# Videre.net
KiCad netlist of a schematic drawn in EAGLE
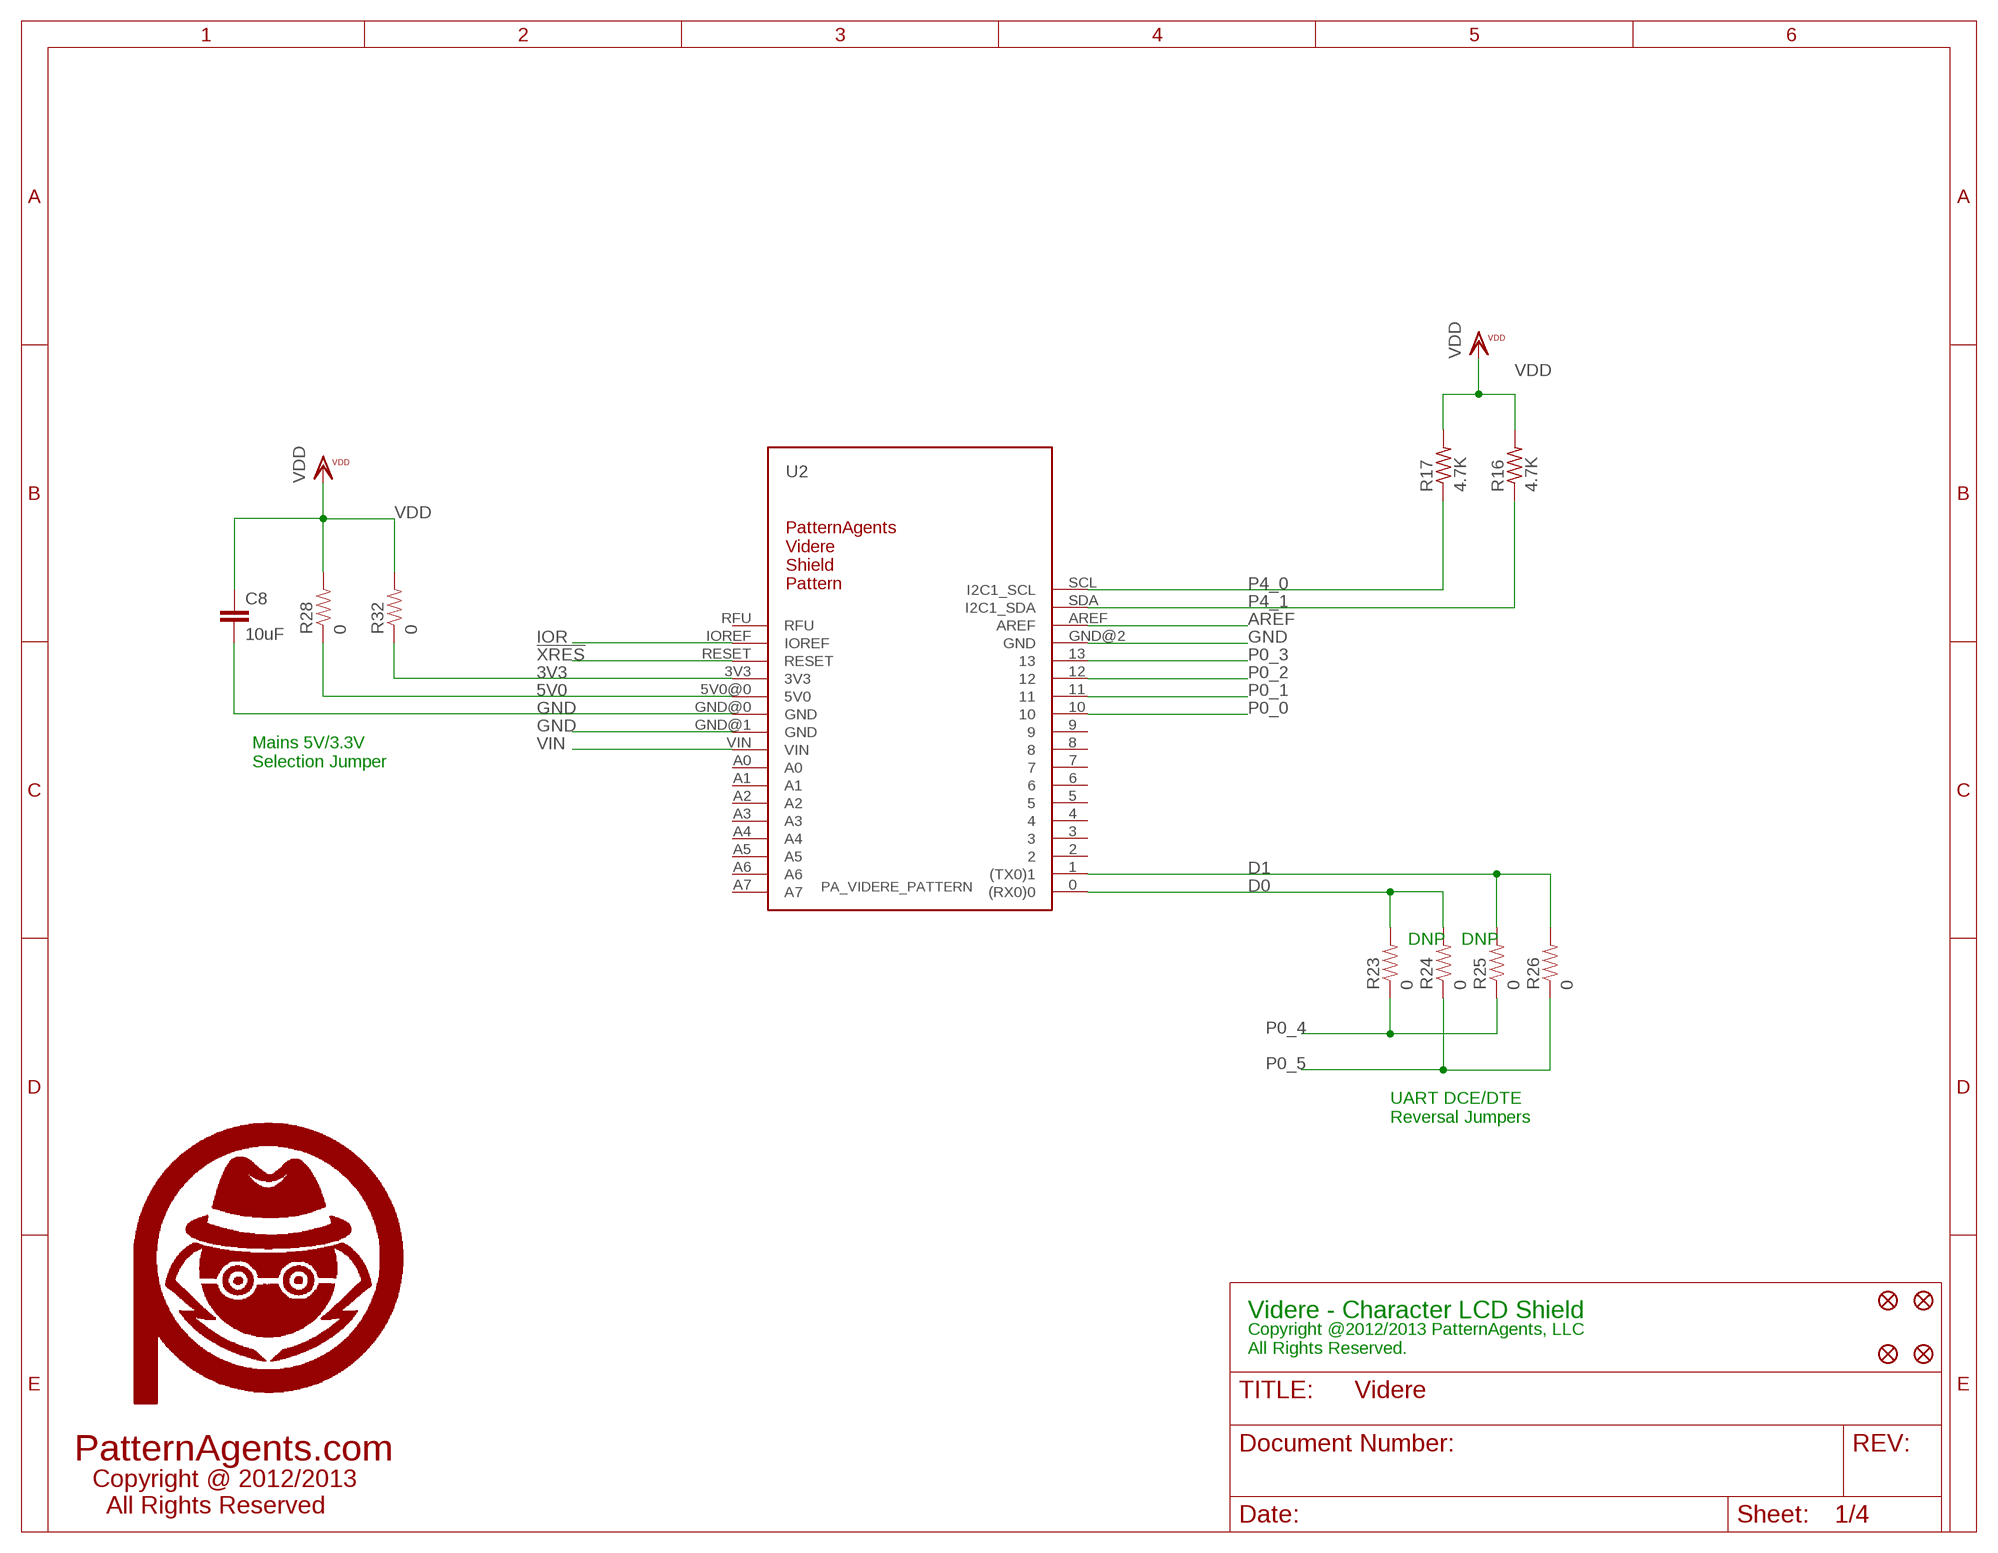
[diagram p0: schematic, sheet 1]
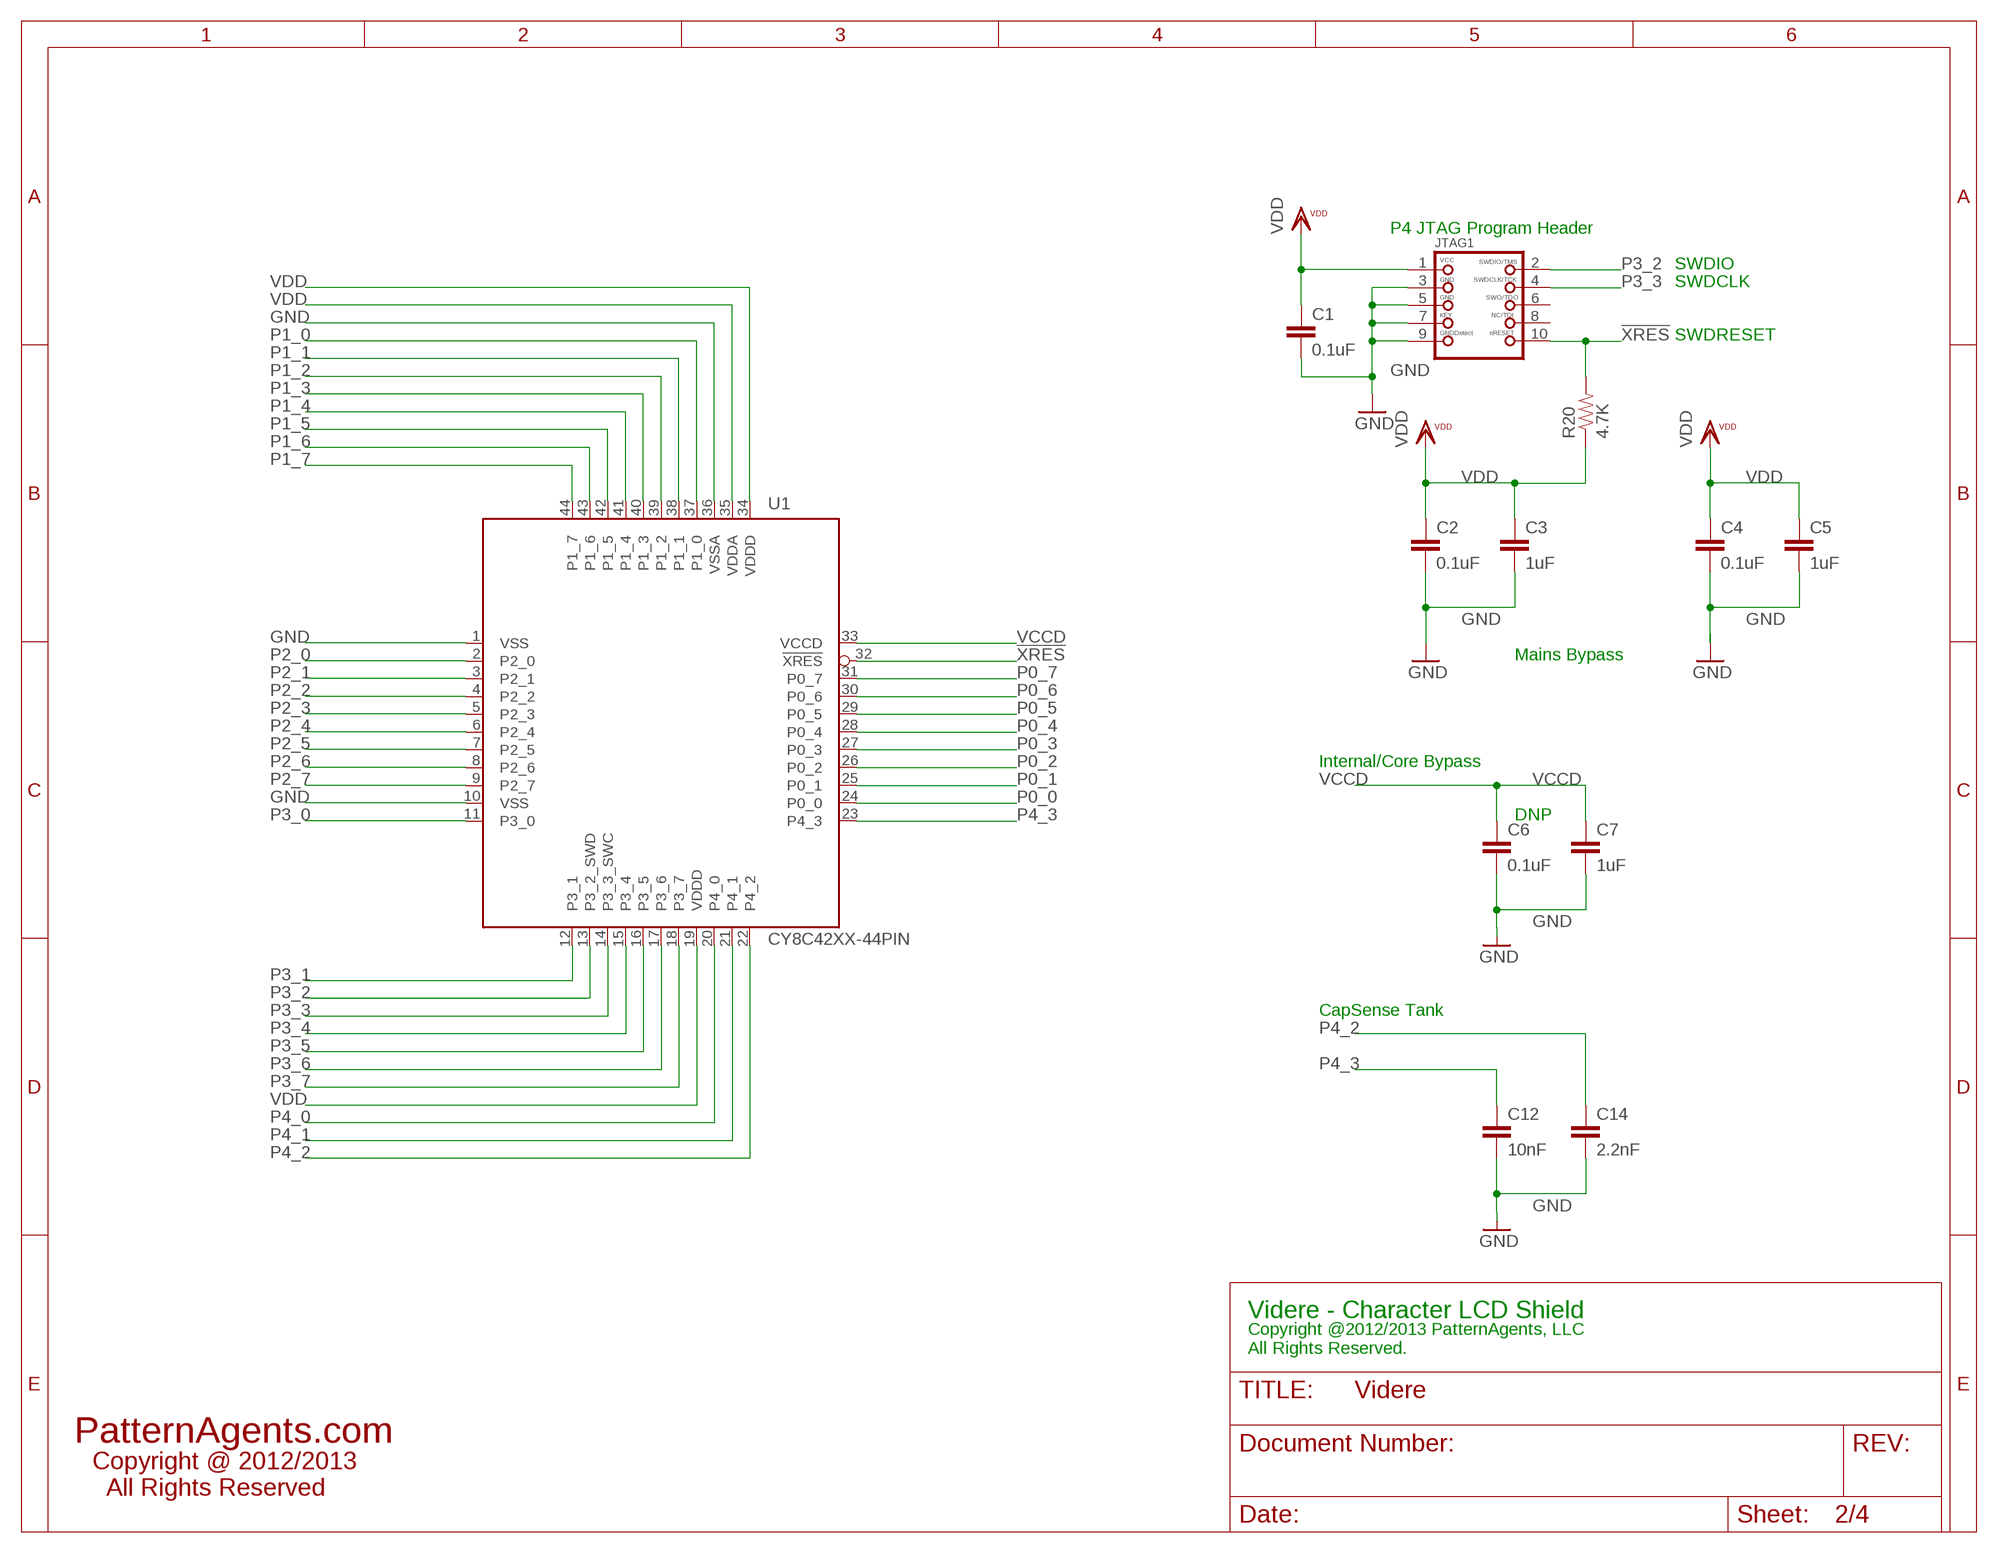
[diagram p1: schematic, sheet 2]
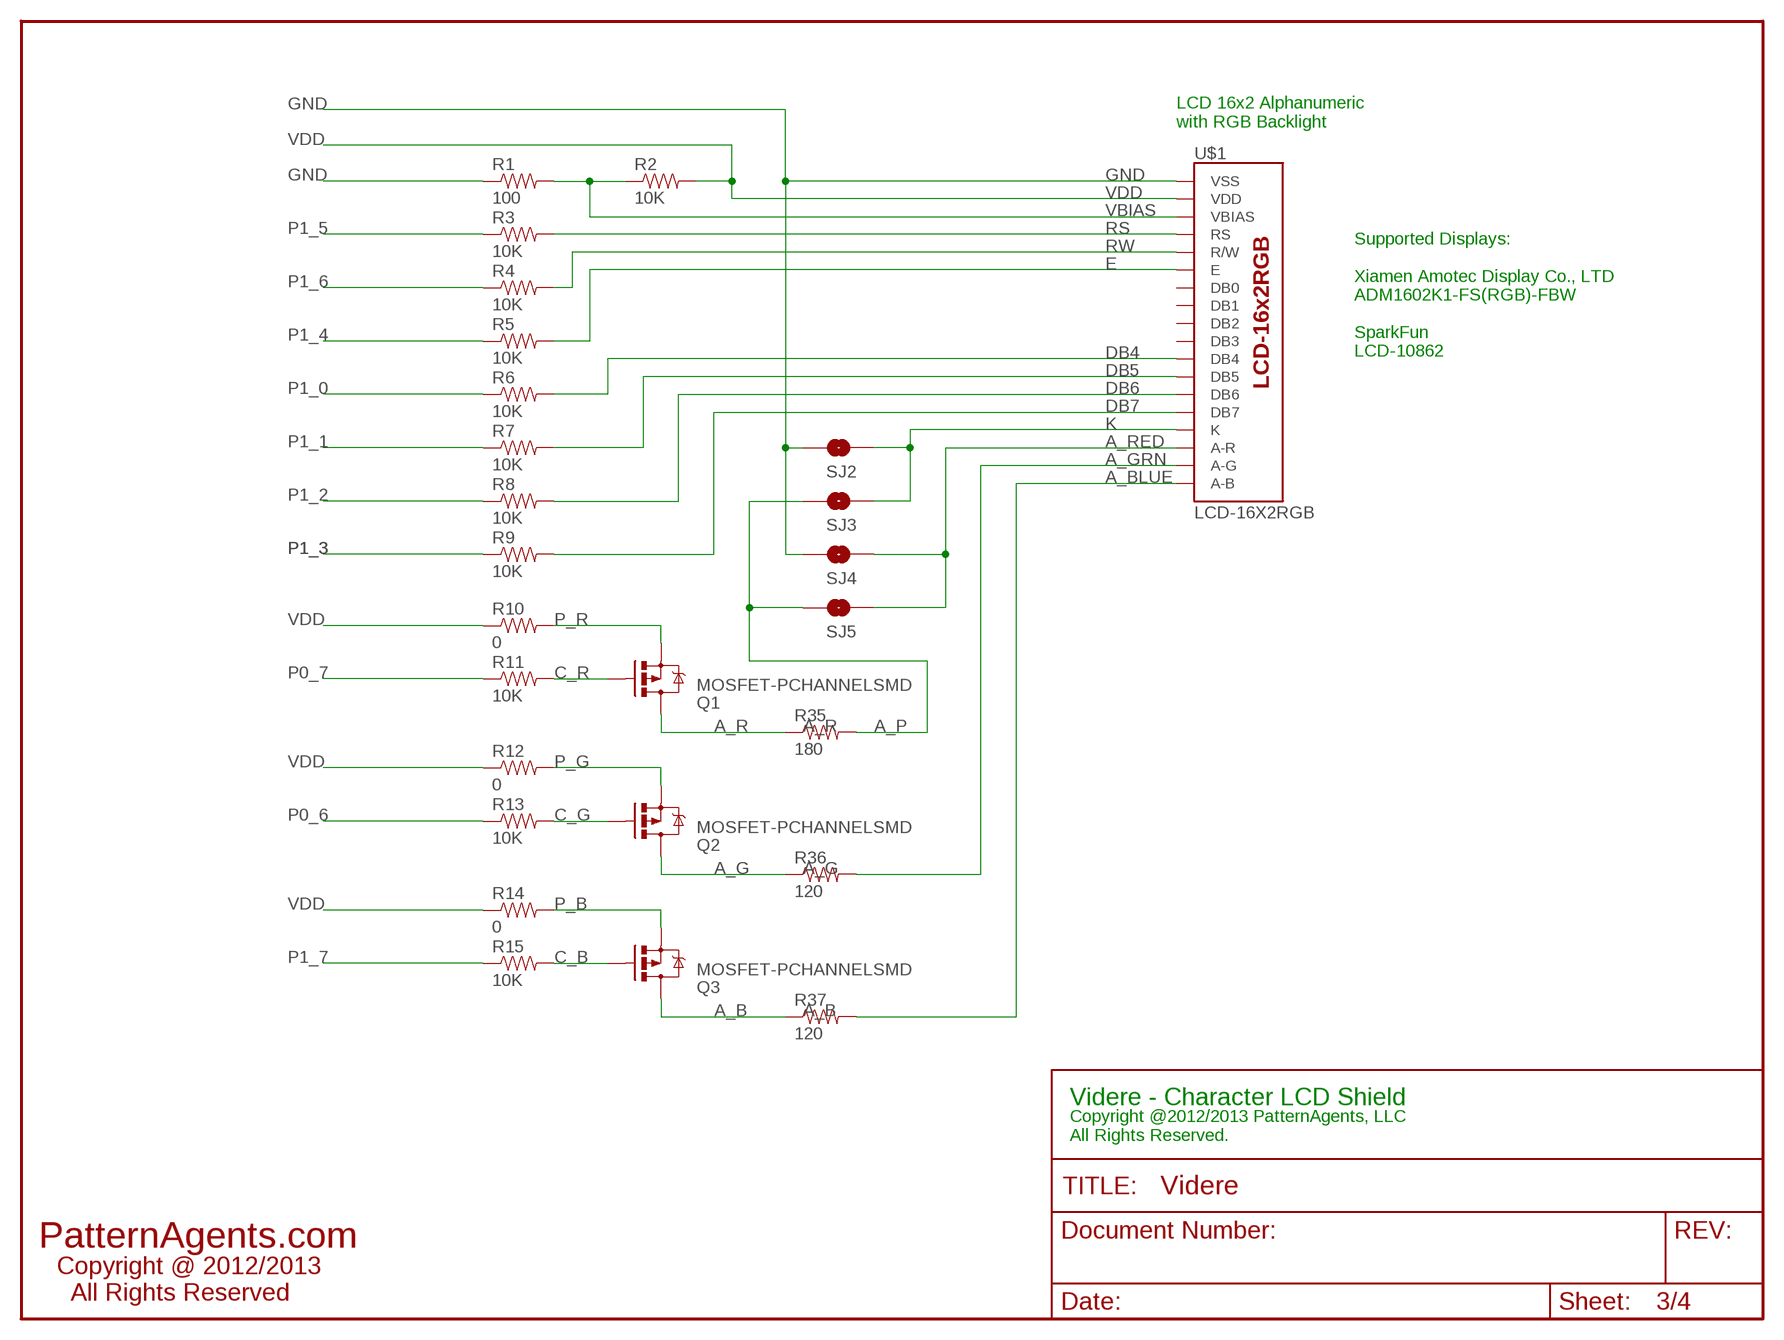
[diagram p2: schematic, sheet 3]
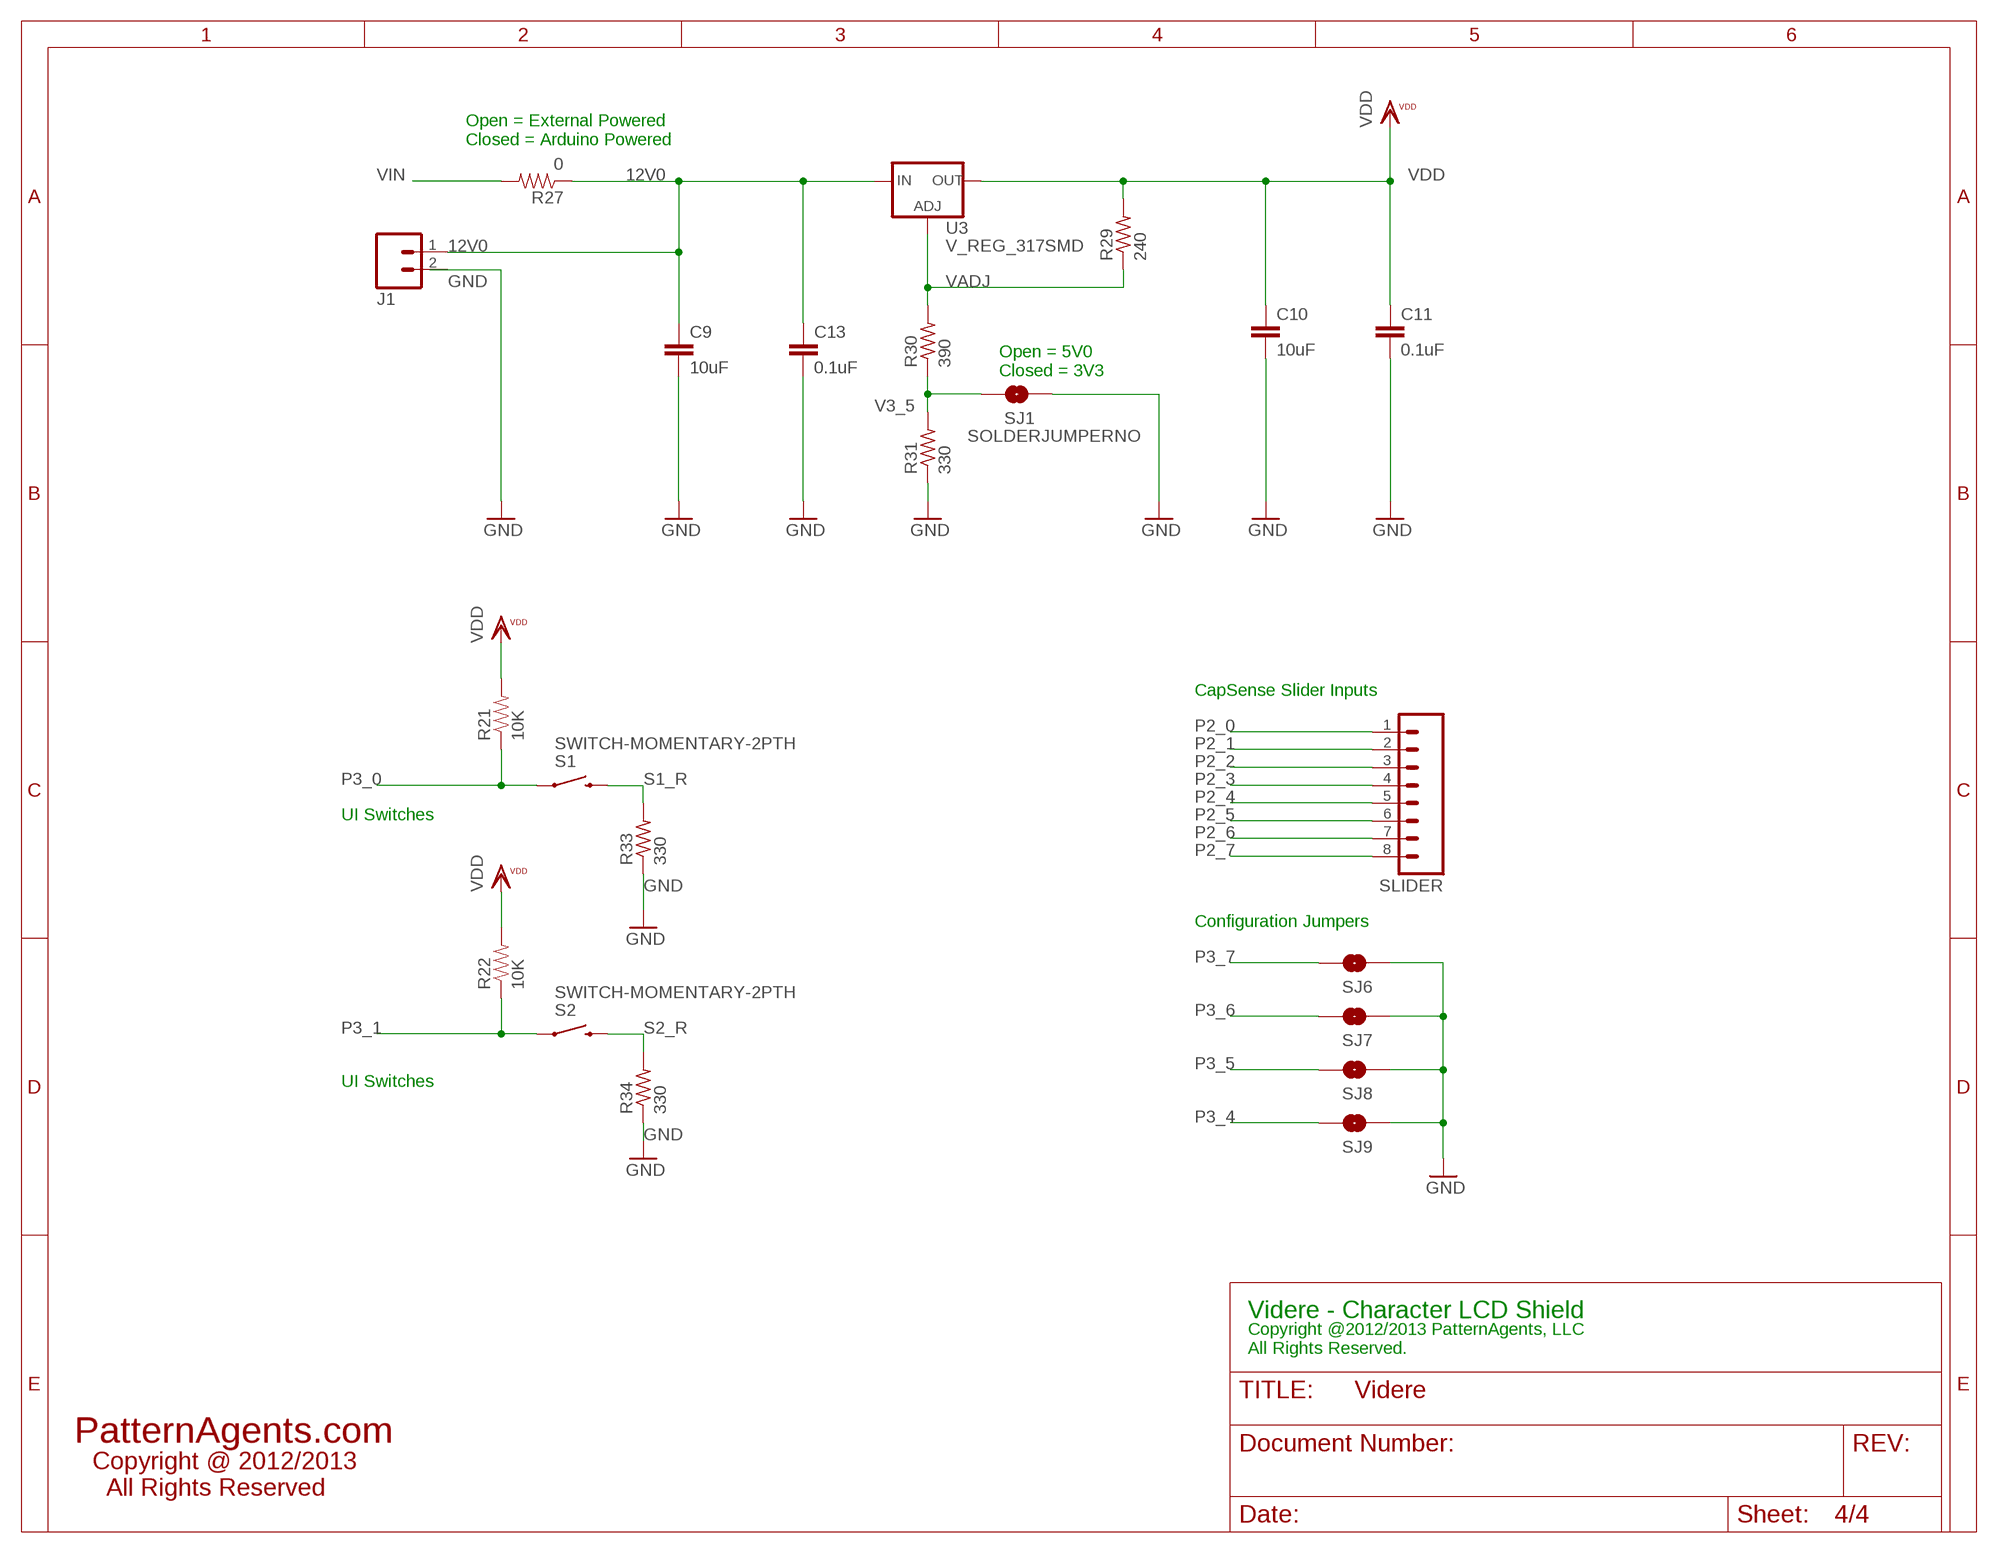
[diagram p3: schematic, sheet 4]

(export (version "E")
  (design (tool "Eeschema 10.0.6"))
  (components
    (comp (ref "C1")
      (value "0.1uF")
      (footprint "eagle-import:0603-CAP")
      (libsource (lib "eagle-import") (part "CAP0603-CAP"))
    )
    (comp (ref "C2")
      (value "0.1uF")
      (footprint "eagle-import:0603-CAP")
      (libsource (lib "eagle-import") (part "CAP0603-CAP"))
    )
    (comp (ref "C3")
      (value "1uF")
      (footprint "eagle-import:0603-CAP")
      (libsource (lib "eagle-import") (part "CAP0603-CAP"))
    )
    (comp (ref "C4")
      (value "0.1uF")
      (footprint "eagle-import:0603-CAP")
      (libsource (lib "eagle-import") (part "CAP0603-CAP"))
    )
    (comp (ref "C5")
      (value "1uF")
      (footprint "eagle-import:0603-CAP")
      (libsource (lib "eagle-import") (part "CAP0603-CAP"))
    )
    (comp (ref "C6")
      (value "0.1uF")
      (footprint "eagle-import:0603-CAP")
      (libsource (lib "eagle-import") (part "CAP0603-CAP"))
    )
    (comp (ref "C7")
      (value "1uF")
      (footprint "eagle-import:0603-CAP")
      (libsource (lib "eagle-import") (part "CAP0603-CAP"))
    )
    (comp (ref "C12")
      (value "10nF")
      (footprint "eagle-import:0603-CAP")
      (libsource (lib "eagle-import") (part "CAP0603-CAP"))
    )
    (comp (ref "C14")
      (value "2.2nF")
      (footprint "eagle-import:0603-CAP")
      (libsource (lib "eagle-import") (part "CAP0603-CAP"))
    )
    (comp (ref "JTAG1")
      (value "JTAG-CORTEXM3")
      (footprint "eagle-import:2X05_1.27MM_SMT")
      (libsource (lib "eagle-import") (part "JTAG-CORTEXM3"))
    )
    (comp (ref "R20")
      (value "4.7K")
      (footprint "eagle-import:0603-RES")
      (libsource (lib "eagle-import") (part "RESISTOR_SFE0603-RES"))
    )
    (comp (ref "U1")
      (value "CY8C42XX-44PIN")
      (footprint "eagle-import:TQFP-10X10-44")
      (libsource (lib "eagle-import") (part "CY8C42XX-44PIN"))
    )
    (comp (ref "Q1")
      (value "MOSFET-PCHANNELSMD")
      (footprint "eagle-import:SOT23-3")
      (libsource (lib "eagle-import") (part "MOSFET-PCHANNELSMD"))
    )
    (comp (ref "Q2")
      (value "MOSFET-PCHANNELSMD")
      (footprint "eagle-import:SOT23-3")
      (libsource (lib "eagle-import") (part "MOSFET-PCHANNELSMD"))
    )
    (comp (ref "Q3")
      (value "MOSFET-PCHANNELSMD")
      (footprint "eagle-import:SOT23-3")
      (libsource (lib "eagle-import") (part "MOSFET-PCHANNELSMD"))
    )
    (comp (ref "R1")
      (value "100")
      (footprint "eagle-import:0603-RES")
      (libsource (lib "eagle-import") (part "RESISTOR_SFE0603-RES"))
    )
    (comp (ref "R2")
      (value "10K")
      (footprint "eagle-import:0603-RES")
      (libsource (lib "eagle-import") (part "RESISTOR_SFE0603-RES"))
    )
    (comp (ref "R3")
      (value "10K")
      (footprint "eagle-import:0603-RES")
      (libsource (lib "eagle-import") (part "RESISTOR_SFE0603-RES"))
    )
    (comp (ref "R4")
      (value "10K")
      (footprint "eagle-import:0603-RES")
      (libsource (lib "eagle-import") (part "RESISTOR_SFE0603-RES"))
    )
    (comp (ref "R5")
      (value "10K")
      (footprint "eagle-import:0603-RES")
      (libsource (lib "eagle-import") (part "RESISTOR_SFE0603-RES"))
    )
    (comp (ref "R6")
      (value "10K")
      (footprint "eagle-import:0603-RES")
      (libsource (lib "eagle-import") (part "RESISTOR_SFE0603-RES"))
    )
    (comp (ref "R7")
      (value "10K")
      (footprint "eagle-import:0603-RES")
      (libsource (lib "eagle-import") (part "RESISTOR_SFE0603-RES"))
    )
    (comp (ref "R8")
      (value "10K")
      (footprint "eagle-import:0603-RES")
      (libsource (lib "eagle-import") (part "RESISTOR_SFE0603-RES"))
    )
    (comp (ref "R9")
      (value "10K")
      (footprint "eagle-import:0603-RES")
      (libsource (lib "eagle-import") (part "RESISTOR_SFE0603-RES"))
    )
    (comp (ref "R10")
      (value "0")
      (footprint "eagle-import:0603-RES")
      (libsource (lib "eagle-import") (part "RESISTOR_SFE0603-RES"))
    )
    (comp (ref "R11")
      (value "10K")
      (footprint "eagle-import:0603-RES")
      (libsource (lib "eagle-import") (part "RESISTOR_SFE0603-RES"))
    )
    (comp (ref "R12")
      (value "0")
      (footprint "eagle-import:0603-RES")
      (libsource (lib "eagle-import") (part "RESISTOR_SFE0603-RES"))
    )
    (comp (ref "R13")
      (value "10K")
      (footprint "eagle-import:0603-RES")
      (libsource (lib "eagle-import") (part "RESISTOR_SFE0603-RES"))
    )
    (comp (ref "R14")
      (value "0")
      (footprint "eagle-import:0603-RES")
      (libsource (lib "eagle-import") (part "RESISTOR_SFE0603-RES"))
    )
    (comp (ref "R15")
      (value "10K")
      (footprint "eagle-import:0603-RES")
      (libsource (lib "eagle-import") (part "RESISTOR_SFE0603-RES"))
    )
    (comp (ref "R35")
      (value "180")
      (footprint "eagle-import:0603-RES")
      (libsource (lib "eagle-import") (part "RESISTOR_SFE0603-RES"))
    )
    (comp (ref "R36")
      (value "120")
      (footprint "eagle-import:0603-RES")
      (libsource (lib "eagle-import") (part "RESISTOR_SFE0603-RES"))
    )
    (comp (ref "R37")
      (value "120")
      (footprint "eagle-import:0603-RES")
      (libsource (lib "eagle-import") (part "RESISTOR_SFE0603-RES"))
    )
    (comp (ref "SJ2")
      (value "SOLDERJUMPERNO")
      (footprint "eagle-import:SJ_2S-NO")
      (libsource (lib "eagle-import") (part "SOLDERJUMPERNO"))
    )
    (comp (ref "SJ3")
      (value "SOLDERJUMPERNO")
      (footprint "eagle-import:SJ_2S-NO")
      (libsource (lib "eagle-import") (part "SOLDERJUMPERNO"))
    )
    (comp (ref "SJ4")
      (value "SOLDERJUMPERNO")
      (footprint "eagle-import:SJ_2S-NO")
      (libsource (lib "eagle-import") (part "SOLDERJUMPERNO"))
    )
    (comp (ref "SJ5")
      (value "SOLDERJUMPERNO")
      (footprint "eagle-import:SJ_2S-NO")
      (libsource (lib "eagle-import") (part "SOLDERJUMPERNO"))
    )
    (comp (ref "U$1")
      (value "LCD-16X2RGB")
      (footprint "eagle-import:LCD-16X2RGB")
      (libsource (lib "eagle-import") (part "LCD-16X2RGB"))
    )
    (comp (ref "C9")
      (value "10uF")
      (footprint "eagle-import:1210")
      (libsource (lib "eagle-import") (part "CAP1210"))
    )
    (comp (ref "C10")
      (value "10uF")
      (footprint "eagle-import:1210")
      (libsource (lib "eagle-import") (part "CAP1210"))
    )
    (comp (ref "C11")
      (value "0.1uF")
      (footprint "eagle-import:0603-CAP")
      (libsource (lib "eagle-import") (part "CAP0603-CAP"))
    )
    (comp (ref "C13")
      (value "0.1uF")
      (footprint "eagle-import:0603-CAP")
      (libsource (lib "eagle-import") (part "CAP0603-CAP"))
    )
    (comp (ref "J1")
      (value "M02PTH")
      (footprint "eagle-import:1X02")
      (libsource (lib "eagle-import") (part "M02PTH"))
    )
    (comp (ref "R21")
      (value "10K")
      (footprint "eagle-import:0603-RES")
      (libsource (lib "eagle-import") (part "RESISTOR_SFE0603-RES"))
    )
    (comp (ref "R22")
      (value "10K")
      (footprint "eagle-import:0603-RES")
      (libsource (lib "eagle-import") (part "RESISTOR_SFE0603-RES"))
    )
    (comp (ref "R27")
      (value "0")
      (footprint "eagle-import:0603-RES")
      (libsource (lib "eagle-import") (part "RESISTOR_SFE0603-RES"))
    )
    (comp (ref "R29")
      (value "240")
      (footprint "eagle-import:R0603")
      (libsource (lib "eagle-import") (part "RESISTORR0603"))
    )
    (comp (ref "R30")
      (value "390")
      (footprint "eagle-import:R0603")
      (libsource (lib "eagle-import") (part "RESISTORR0603"))
    )
    (comp (ref "R31")
      (value "330")
      (footprint "eagle-import:R0603")
      (libsource (lib "eagle-import") (part "RESISTORR0603"))
    )
    (comp (ref "R33")
      (value "330")
      (footprint "eagle-import:R0603")
      (libsource (lib "eagle-import") (part "RESISTORR0603"))
    )
    (comp (ref "R34")
      (value "330")
      (footprint "eagle-import:R0603")
      (libsource (lib "eagle-import") (part "RESISTORR0603"))
    )
    (comp (ref "S1")
      (value "SWITCH-MOMENTARY-2PTH")
      (footprint "eagle-import:TACTILE-PTH")
      (libsource (lib "eagle-import") (part "SWITCH-MOMENTARY-2PTH"))
    )
    (comp (ref "S2")
      (value "SWITCH-MOMENTARY-2PTH")
      (footprint "eagle-import:TACTILE-PTH")
      (libsource (lib "eagle-import") (part "SWITCH-MOMENTARY-2PTH"))
    )
    (comp (ref "SJ1")
      (value "SOLDERJUMPERNO")
      (footprint "eagle-import:SJ_2S-NO")
      (libsource (lib "eagle-import") (part "SOLDERJUMPERNO"))
    )
    (comp (ref "SJ6")
      (value "SOLDERJUMPERNO")
      (footprint "eagle-import:SJ_2S-NO")
      (libsource (lib "eagle-import") (part "SOLDERJUMPERNO"))
    )
    (comp (ref "SJ7")
      (value "SOLDERJUMPERNO")
      (footprint "eagle-import:SJ_2S-NO")
      (libsource (lib "eagle-import") (part "SOLDERJUMPERNO"))
    )
    (comp (ref "SJ8")
      (value "SOLDERJUMPERNO")
      (footprint "eagle-import:SJ_2S-NO")
      (libsource (lib "eagle-import") (part "SOLDERJUMPERNO"))
    )
    (comp (ref "SJ9")
      (value "SOLDERJUMPERNO")
      (footprint "eagle-import:SJ_2S-NO")
      (libsource (lib "eagle-import") (part "SOLDERJUMPERNO"))
    )
    (comp (ref "SLIDER")
      (value "M081X08")
      (footprint "eagle-import:1X08")
      (libsource (lib "eagle-import") (part "M081X08"))
    )
    (comp (ref "U3")
      (value "V_REG_317SMD")
      (footprint "eagle-import:SOT223")
      (libsource (lib "eagle-import") (part "V_REG_317SMD"))
    )
    (comp (ref "C8")
      (value "10uF")
      (footprint "eagle-import:1210")
      (libsource (lib "eagle-import") (part "CAP1210"))
    )
    (comp (ref "FID1")
      (value "FIDUCIAL1.5X3")
      (footprint "eagle-import:FIDUCIAL-1.5X3")
      (libsource (lib "eagle-import") (part "FIDUCIAL1.5X3"))
    )
    (comp (ref "FID2")
      (value "FIDUCIAL1.5X3")
      (footprint "eagle-import:FIDUCIAL-1.5X3")
      (libsource (lib "eagle-import") (part "FIDUCIAL1.5X3"))
    )
    (comp (ref "FID3")
      (value "FIDUCIAL1.5X3")
      (footprint "eagle-import:FIDUCIAL-1.5X3")
      (libsource (lib "eagle-import") (part "FIDUCIAL1.5X3"))
    )
    (comp (ref "FID4")
      (value "FIDUCIAL1.5X3")
      (footprint "eagle-import:FIDUCIAL-1.5X3")
      (libsource (lib "eagle-import") (part "FIDUCIAL1.5X3"))
    )
    (comp (ref "R16")
      (value "4.7K")
      (footprint "eagle-import:R0603")
      (libsource (lib "eagle-import") (part "RESISTORR0603"))
    )
    (comp (ref "R17")
      (value "4.7K")
      (footprint "eagle-import:R0603")
      (libsource (lib "eagle-import") (part "RESISTORR0603"))
    )
    (comp (ref "R23")
      (value "0")
      (footprint "eagle-import:0603-RES")
      (libsource (lib "eagle-import") (part "RESISTOR_SFE0603-RES"))
    )
    (comp (ref "R24")
      (value "0")
      (footprint "eagle-import:0603-RES")
      (libsource (lib "eagle-import") (part "RESISTOR_SFE0603-RES"))
    )
    (comp (ref "R25")
      (value "0")
      (footprint "eagle-import:0603-RES")
      (libsource (lib "eagle-import") (part "RESISTOR_SFE0603-RES"))
    )
    (comp (ref "R26")
      (value "0")
      (footprint "eagle-import:0603-RES")
      (libsource (lib "eagle-import") (part "RESISTOR_SFE0603-RES"))
    )
    (comp (ref "R28")
      (value "0")
      (footprint "eagle-import:0603-RES@1")
      (libsource (lib "eagle-import") (part "moxdes_std_RESISTOR_SFE0603-RES"))
    )
    (comp (ref "R32")
      (value "0")
      (footprint "eagle-import:0603-RES@1")
      (libsource (lib "eagle-import") (part "moxdes_std_RESISTOR_SFE0603-RES"))
    )
    (comp (ref "U$3")
      (value "PA_LOGO_SYMLARGE")
      (footprint "eagle-import:PA_LOGO_AGENT_LRG_SYM")
      (libsource (lib "eagle-import") (part "PA_LOGO_SYMLARGE"))
    )
    (comp (ref "U2")
      (value "PA_VIDERE_PATTERN")
      (footprint "eagle-import:PA_VIDERE_PATTERN")
      (libsource (lib "eagle-import") (part "PA_VIDERE_PATTERN"))
    )
  )
  (nets
    (net (code "1") (name "3V3") (class "Default")
      (node (ref "R32") (pin "1") (pinfunction "1_1") (pintype "passive"))
      (node (ref "U2") (pin "3V3") (pinfunction "3V3_3V3") (pintype "bidirectional"))
    )
    (net (code "2") (name "5V0") (class "Default")
      (node (ref "R28") (pin "1") (pinfunction "1_1") (pintype "passive"))
      (node (ref "U2") (pin "5V0@0") (pinfunction "5V0_5V0@0") (pintype "bidirectional"))
    )
    (net (code "3") (name "12V0") (class "Default")
      (node (ref "C13") (pin "1") (pinfunction "1_1") (pintype "passive"))
      (node (ref "C9") (pin "1") (pinfunction "1_1") (pintype "passive"))
      (node (ref "J1") (pin "1") (pinfunction "1_1") (pintype "passive"))
      (node (ref "R27") (pin "1") (pinfunction "1_1") (pintype "passive"))
      (node (ref "U3") (pin "3") (pinfunction "IN_3") (pintype "input"))
    )
    (net (code "4") (name "AREF") (class "Default")
      (node (ref "U2") (pin "AREF") (pinfunction "AREF_AREF") (pintype "bidirectional"))
    )
    (net (code "5") (name "A_B") (class "Default")
      (node (ref "Q3") (pin "3") (pinfunction "D_3") (pintype "passive"))
      (node (ref "R37") (pin "1") (pinfunction "1_1") (pintype "passive"))
    )
    (net (code "6") (name "A_BLUE") (class "Default")
      (node (ref "R37") (pin "2") (pinfunction "2_2") (pintype "passive"))
      (node (ref "U$1") (pin "18") (pinfunction "A-B_18") (pintype "power_in"))
    )
    (net (code "7") (name "A_G") (class "Default")
      (node (ref "Q2") (pin "3") (pinfunction "D_3") (pintype "passive"))
      (node (ref "R36") (pin "1") (pinfunction "1_1") (pintype "passive"))
    )
    (net (code "8") (name "A_GRN") (class "Default")
      (node (ref "R36") (pin "2") (pinfunction "2_2") (pintype "passive"))
      (node (ref "U$1") (pin "17") (pinfunction "A-G_17") (pintype "power_in"))
    )
    (net (code "9") (name "A_P") (class "Default")
      (node (ref "R35") (pin "2") (pinfunction "2_2") (pintype "passive"))
      (node (ref "SJ3") (pin "2") (pinfunction "2_2") (pintype "passive"))
      (node (ref "SJ5") (pin "2") (pinfunction "2_2") (pintype "passive"))
    )
    (net (code "10") (name "A_R") (class "Default")
      (node (ref "Q1") (pin "3") (pinfunction "D_3") (pintype "passive"))
      (node (ref "R35") (pin "1") (pinfunction "1_1") (pintype "passive"))
    )
    (net (code "11") (name "A_RED") (class "Default")
      (node (ref "SJ4") (pin "1") (pinfunction "1_1") (pintype "passive"))
      (node (ref "SJ5") (pin "1") (pinfunction "1_1") (pintype "passive"))
      (node (ref "U$1") (pin "16") (pinfunction "A-R_16") (pintype "power_in"))
    )
    (net (code "12") (name "C_B") (class "Default")
      (node (ref "Q3") (pin "1") (pinfunction "G_1") (pintype "passive"))
      (node (ref "R15") (pin "2") (pinfunction "2_2") (pintype "passive"))
    )
    (net (code "13") (name "C_G") (class "Default")
      (node (ref "Q2") (pin "1") (pinfunction "G_1") (pintype "passive"))
      (node (ref "R13") (pin "2") (pinfunction "2_2") (pintype "passive"))
    )
    (net (code "14") (name "C_R") (class "Default")
      (node (ref "Q1") (pin "1") (pinfunction "G_1") (pintype "passive"))
      (node (ref "R11") (pin "2") (pinfunction "2_2") (pintype "passive"))
    )
    (net (code "15") (name "D0") (class "Default")
      (node (ref "R23") (pin "2") (pinfunction "2_2") (pintype "passive"))
      (node (ref "R24") (pin "2") (pinfunction "2_2") (pintype "passive"))
      (node (ref "U2") (pin "0") (pinfunction "(RX0)0_0") (pintype "bidirectional"))
    )
    (net (code "16") (name "D1") (class "Default")
      (node (ref "R25") (pin "2") (pinfunction "2_2") (pintype "passive"))
      (node (ref "R26") (pin "2") (pinfunction "2_2") (pintype "passive"))
      (node (ref "U2") (pin "1") (pinfunction "(TX0)1_1") (pintype "bidirectional"))
    )
    (net (code "17") (name "DB4") (class "Default")
      (node (ref "R6") (pin "2") (pinfunction "2_2") (pintype "passive"))
      (node (ref "U$1") (pin "11") (pinfunction "DB4_11") (pintype "bidirectional"))
    )
    (net (code "18") (name "DB5") (class "Default")
      (node (ref "R7") (pin "2") (pinfunction "2_2") (pintype "passive"))
      (node (ref "U$1") (pin "12") (pinfunction "DB5_12") (pintype "bidirectional"))
    )
    (net (code "19") (name "DB6") (class "Default")
      (node (ref "R8") (pin "2") (pinfunction "2_2") (pintype "passive"))
      (node (ref "U$1") (pin "13") (pinfunction "DB6_13") (pintype "bidirectional"))
    )
    (net (code "20") (name "DB7") (class "Default")
      (node (ref "R9") (pin "2") (pinfunction "2_2") (pintype "passive"))
      (node (ref "U$1") (pin "14") (pinfunction "DB7_14") (pintype "bidirectional"))
    )
    (net (code "21") (name "E") (class "Default")
      (node (ref "R5") (pin "2") (pinfunction "2_2") (pintype "passive"))
      (node (ref "U$1") (pin "6") (pinfunction "E_6") (pintype "input"))
    )
    (net (code "22") (name "GND") (class "Default")
      (node (ref "C1") (pin "2") (pinfunction "2_2") (pintype "passive"))
      (node (ref "C10") (pin "2") (pinfunction "2_2") (pintype "passive"))
      (node (ref "C11") (pin "2") (pinfunction "2_2") (pintype "passive"))
      (node (ref "C12") (pin "2") (pinfunction "2_2") (pintype "passive"))
      (node (ref "C13") (pin "2") (pinfunction "2_2") (pintype "passive"))
      (node (ref "C14") (pin "2") (pinfunction "2_2") (pintype "passive"))
      (node (ref "C2") (pin "2") (pinfunction "2_2") (pintype "passive"))
      (node (ref "C3") (pin "2") (pinfunction "2_2") (pintype "passive"))
      (node (ref "C4") (pin "2") (pinfunction "2_2") (pintype "passive"))
      (node (ref "C5") (pin "2") (pinfunction "2_2") (pintype "passive"))
      (node (ref "C6") (pin "2") (pinfunction "2_2") (pintype "passive"))
      (node (ref "C7") (pin "2") (pinfunction "2_2") (pintype "passive"))
      (node (ref "C8") (pin "2") (pinfunction "2_2") (pintype "passive"))
      (node (ref "C9") (pin "2") (pinfunction "2_2") (pintype "passive"))
      (node (ref "J1") (pin "2") (pinfunction "2_2") (pintype "passive"))
      (node (ref "JTAG1") (pin "3") (pinfunction "3_3") (pintype "passive"))
      (node (ref "JTAG1") (pin "5") (pinfunction "5_5") (pintype "passive"))
      (node (ref "JTAG1") (pin "7") (pinfunction "7_7") (pintype "passive"))
      (node (ref "JTAG1") (pin "9") (pinfunction "9_9") (pintype "passive"))
      (node (ref "R1") (pin "1") (pinfunction "1_1") (pintype "passive"))
      (node (ref "R31") (pin "1") (pinfunction "1_1") (pintype "passive"))
      (node (ref "R33") (pin "1") (pinfunction "1_1") (pintype "passive"))
      (node (ref "R34") (pin "1") (pinfunction "1_1") (pintype "passive"))
      (node (ref "SJ1") (pin "1") (pinfunction "1_1") (pintype "passive"))
      (node (ref "SJ2") (pin "2") (pinfunction "2_2") (pintype "passive"))
      (node (ref "SJ4") (pin "2") (pinfunction "2_2") (pintype "passive"))
      (node (ref "SJ6") (pin "1") (pinfunction "1_1") (pintype "passive"))
      (node (ref "SJ7") (pin "1") (pinfunction "1_1") (pintype "passive"))
      (node (ref "SJ8") (pin "1") (pinfunction "1_1") (pintype "passive"))
      (node (ref "SJ9") (pin "1") (pinfunction "1_1") (pintype "passive"))
      (node (ref "U$1") (pin "1") (pinfunction "VSS_1") (pintype "power_in"))
      (node (ref "U1") (pin "1") (pinfunction "VSS_1") (pintype "bidirectional"))
      (node (ref "U1") (pin "10") (pinfunction "VSS_10") (pintype "bidirectional"))
      (node (ref "U1") (pin "36") (pinfunction "VSSA_36") (pintype "bidirectional"))
      (node (ref "U2") (pin "GND@0") (pinfunction "GND_GND@0") (pintype "bidirectional"))
      (node (ref "U2") (pin "GND@1") (pinfunction "GND_GND@1") (pintype "bidirectional"))
      (node (ref "U2") (pin "GND@2") (pinfunction "GND_GND@2") (pintype "bidirectional"))
    )
    (net (code "23") (name "IOR") (class "Default")
      (node (ref "U2") (pin "IOREF") (pinfunction "IOREF_IOREF") (pintype "output"))
    )
    (net (code "24") (name "K") (class "Default")
      (node (ref "SJ2") (pin "1") (pinfunction "1_1") (pintype "passive"))
      (node (ref "SJ3") (pin "1") (pinfunction "1_1") (pintype "passive"))
      (node (ref "U$1") (pin "15") (pinfunction "K_15") (pintype "power_in"))
    )
    (net (code "25") (name "P0_0") (class "Default")
      (node (ref "U1") (pin "24") (pinfunction "P0_0_24") (pintype "bidirectional"))
      (node (ref "U2") (pin "10") (pinfunction "10_10") (pintype "bidirectional"))
    )
    (net (code "26") (name "P0_1") (class "Default")
      (node (ref "U1") (pin "25") (pinfunction "P0_1_25") (pintype "bidirectional"))
      (node (ref "U2") (pin "11") (pinfunction "11_11") (pintype "bidirectional"))
    )
    (net (code "27") (name "P0_2") (class "Default")
      (node (ref "U1") (pin "26") (pinfunction "P0_2_26") (pintype "input"))
      (node (ref "U2") (pin "12") (pinfunction "12_12") (pintype "bidirectional"))
    )
    (net (code "28") (name "P0_3") (class "Default")
      (node (ref "U1") (pin "27") (pinfunction "P0_3_27") (pintype "bidirectional"))
      (node (ref "U2") (pin "13") (pinfunction "13_13") (pintype "bidirectional"))
    )
    (net (code "29") (name "P0_4") (class "Default")
      (node (ref "R23") (pin "1") (pinfunction "1_1") (pintype "passive"))
      (node (ref "R25") (pin "1") (pinfunction "1_1") (pintype "passive"))
      (node (ref "U1") (pin "28") (pinfunction "P0_4_28") (pintype "bidirectional"))
    )
    (net (code "30") (name "P0_5") (class "Default")
      (node (ref "R24") (pin "1") (pinfunction "1_1") (pintype "passive"))
      (node (ref "R26") (pin "1") (pinfunction "1_1") (pintype "passive"))
      (node (ref "U1") (pin "29") (pinfunction "P0_5_29") (pintype "bidirectional"))
    )
    (net (code "31") (name "P0_6") (class "Default")
      (node (ref "R13") (pin "1") (pinfunction "1_1") (pintype "passive"))
      (node (ref "U1") (pin "30") (pinfunction "P0_6_30") (pintype "power_in"))
    )
    (net (code "32") (name "P0_7") (class "Default")
      (node (ref "R11") (pin "1") (pinfunction "1_1") (pintype "passive"))
      (node (ref "U1") (pin "31") (pinfunction "P0_7_31") (pintype "bidirectional"))
    )
    (net (code "33") (name "P1_0") (class "Default")
      (node (ref "R6") (pin "1") (pinfunction "1_1") (pintype "passive"))
      (node (ref "U1") (pin "37") (pinfunction "P1_0_37") (pintype "bidirectional"))
    )
    (net (code "34") (name "P1_1") (class "Default")
      (node (ref "R7") (pin "1") (pinfunction "1_1") (pintype "passive"))
      (node (ref "U1") (pin "38") (pinfunction "P1_1_38") (pintype "bidirectional"))
    )
    (net (code "35") (name "P1_2") (class "Default")
      (node (ref "R8") (pin "1") (pinfunction "1_1") (pintype "passive"))
      (node (ref "U1") (pin "39") (pinfunction "P1_2_39") (pintype "power_in"))
    )
    (net (code "36") (name "P1_3") (class "Default")
      (node (ref "R9") (pin "1") (pinfunction "1_1") (pintype "passive"))
      (node (ref "U1") (pin "40") (pinfunction "P1_3_40") (pintype "bidirectional"))
    )
    (net (code "37") (name "P1_4") (class "Default")
      (node (ref "R5") (pin "1") (pinfunction "1_1") (pintype "passive"))
      (node (ref "U1") (pin "41") (pinfunction "P1_4_41") (pintype "bidirectional"))
    )
    (net (code "38") (name "P1_5") (class "Default")
      (node (ref "R3") (pin "1") (pinfunction "1_1") (pintype "passive"))
      (node (ref "U1") (pin "42") (pinfunction "P1_5_42") (pintype "bidirectional"))
    )
    (net (code "39") (name "P1_6") (class "Default")
      (node (ref "R4") (pin "1") (pinfunction "1_1") (pintype "passive"))
      (node (ref "U1") (pin "43") (pinfunction "P1_6_43") (pintype "bidirectional"))
    )
    (net (code "40") (name "P1_7") (class "Default")
      (node (ref "R15") (pin "1") (pinfunction "1_1") (pintype "passive"))
      (node (ref "U1") (pin "44") (pinfunction "P1_7_44") (pintype "bidirectional"))
    )
    (net (code "41") (name "P2_0") (class "Default")
      (node (ref "SLIDER") (pin "1") (pinfunction "1_1") (pintype "passive"))
      (node (ref "U1") (pin "2") (pinfunction "P2_0_2") (pintype "bidirectional"))
    )
    (net (code "42") (name "P2_1") (class "Default")
      (node (ref "SLIDER") (pin "2") (pinfunction "2_2") (pintype "passive"))
      (node (ref "U1") (pin "3") (pinfunction "P2_1_3") (pintype "bidirectional"))
    )
    (net (code "43") (name "P2_2") (class "Default")
      (node (ref "SLIDER") (pin "3") (pinfunction "3_3") (pintype "passive"))
      (node (ref "U1") (pin "4") (pinfunction "P2_2_4") (pintype "power_in"))
    )
    (net (code "44") (name "P2_3") (class "Default")
      (node (ref "SLIDER") (pin "4") (pinfunction "4_4") (pintype "passive"))
      (node (ref "U1") (pin "5") (pinfunction "P2_3_5") (pintype "bidirectional"))
    )
    (net (code "45") (name "P2_4") (class "Default")
      (node (ref "SLIDER") (pin "5") (pinfunction "5_5") (pintype "passive"))
      (node (ref "U1") (pin "6") (pinfunction "P2_4_6") (pintype "bidirectional"))
    )
    (net (code "46") (name "P2_5") (class "Default")
      (node (ref "SLIDER") (pin "6") (pinfunction "6_6") (pintype "passive"))
      (node (ref "U1") (pin "7") (pinfunction "P2_5_7") (pintype "bidirectional"))
    )
    (net (code "47") (name "P2_6") (class "Default")
      (node (ref "SLIDER") (pin "7") (pinfunction "7_7") (pintype "passive"))
      (node (ref "U1") (pin "8") (pinfunction "P2_6_8") (pintype "power_in"))
    )
    (net (code "48") (name "P2_7") (class "Default")
      (node (ref "SLIDER") (pin "8") (pinfunction "8_8") (pintype "passive"))
      (node (ref "U1") (pin "9") (pinfunction "P2_7_9") (pintype "bidirectional"))
    )
    (net (code "49") (name "P3_0") (class "Default")
      (node (ref "R21") (pin "1") (pinfunction "1_1") (pintype "passive"))
      (node (ref "S1") (pin "1") (pinfunction "1_1") (pintype "passive"))
      (node (ref "U1") (pin "11") (pinfunction "P3_0_11") (pintype "bidirectional"))
    )
    (net (code "50") (name "P3_1") (class "Default")
      (node (ref "R22") (pin "1") (pinfunction "1_1") (pintype "passive"))
      (node (ref "S2") (pin "1") (pinfunction "1_1") (pintype "passive"))
      (node (ref "U1") (pin "12") (pinfunction "P3_1_12") (pintype "bidirectional"))
    )
    (net (code "51") (name "P3_2") (class "Default")
      (node (ref "JTAG1") (pin "2") (pinfunction "2_2") (pintype "passive"))
      (node (ref "U1") (pin "13") (pinfunction "P3_2_SWD_13") (pintype "bidirectional"))
    )
    (net (code "52") (name "P3_3") (class "Default")
      (node (ref "JTAG1") (pin "4") (pinfunction "4_4") (pintype "passive"))
      (node (ref "U1") (pin "14") (pinfunction "P3_3_SWC_14") (pintype "bidirectional"))
    )
    (net (code "53") (name "P3_4") (class "Default")
      (node (ref "SJ9") (pin "2") (pinfunction "2_2") (pintype "passive"))
      (node (ref "U1") (pin "15") (pinfunction "P3_4_15") (pintype "bidirectional"))
    )
    (net (code "54") (name "P3_5") (class "Default")
      (node (ref "SJ8") (pin "2") (pinfunction "2_2") (pintype "passive"))
      (node (ref "U1") (pin "16") (pinfunction "P3_5_16") (pintype "bidirectional"))
    )
    (net (code "55") (name "P3_6") (class "Default")
      (node (ref "SJ7") (pin "2") (pinfunction "2_2") (pintype "passive"))
      (node (ref "U1") (pin "17") (pinfunction "P3_6_17") (pintype "power_in"))
    )
    (net (code "56") (name "P3_7") (class "Default")
      (node (ref "SJ6") (pin "2") (pinfunction "2_2") (pintype "passive"))
      (node (ref "U1") (pin "18") (pinfunction "P3_7_18") (pintype "bidirectional"))
    )
    (net (code "57") (name "P4_0") (class "Default")
      (node (ref "R17") (pin "1") (pinfunction "1_1") (pintype "passive"))
      (node (ref "U1") (pin "20") (pinfunction "P4_0_20") (pintype "bidirectional"))
      (node (ref "U2") (pin "SCL") (pinfunction "I2C1_SCL_SCL") (pintype "bidirectional"))
    )
    (net (code "58") (name "P4_1") (class "Default")
      (node (ref "R16") (pin "1") (pinfunction "1_1") (pintype "passive"))
      (node (ref "U1") (pin "21") (pinfunction "P4_1_21") (pintype "bidirectional"))
      (node (ref "U2") (pin "SDA") (pinfunction "I2C1_SDA_SDA") (pintype "bidirectional"))
    )
    (net (code "59") (name "P4_2") (class "Default")
      (node (ref "C14") (pin "1") (pinfunction "1_1") (pintype "passive"))
      (node (ref "U1") (pin "22") (pinfunction "P4_2_22") (pintype "bidirectional"))
    )
    (net (code "60") (name "P4_3") (class "Default")
      (node (ref "C12") (pin "1") (pinfunction "1_1") (pintype "passive"))
      (node (ref "U1") (pin "23") (pinfunction "P4_3_23") (pintype "bidirectional"))
    )
    (net (code "61") (name "P_B") (class "Default")
      (node (ref "Q3") (pin "2") (pinfunction "S_2") (pintype "passive"))
      (node (ref "R14") (pin "2") (pinfunction "2_2") (pintype "passive"))
    )
    (net (code "62") (name "P_G") (class "Default")
      (node (ref "Q2") (pin "2") (pinfunction "S_2") (pintype "passive"))
      (node (ref "R12") (pin "2") (pinfunction "2_2") (pintype "passive"))
    )
    (net (code "63") (name "P_R") (class "Default")
      (node (ref "Q1") (pin "2") (pinfunction "S_2") (pintype "passive"))
      (node (ref "R10") (pin "2") (pinfunction "2_2") (pintype "passive"))
    )
    (net (code "64") (name "RFU") (class "Default")
      (node (ref "U2") (pin "RFU") (pinfunction "RFU_RFU") (pintype "power_in"))
    )
    (net (code "65") (name "RS") (class "Default")
      (node (ref "R3") (pin "2") (pinfunction "2_2") (pintype "passive"))
      (node (ref "U$1") (pin "4") (pinfunction "RS_4") (pintype "input"))
    )
    (net (code "66") (name "RW") (class "Default")
      (node (ref "R4") (pin "2") (pinfunction "2_2") (pintype "passive"))
      (node (ref "U$1") (pin "5") (pinfunction "R/W_5") (pintype "input"))
    )
    (net (code "67") (name "S1_R") (class "Default")
      (node (ref "R33") (pin "2") (pinfunction "2_2") (pintype "passive"))
      (node (ref "S1") (pin "3") (pinfunction "2_3") (pintype "passive"))
    )
    (net (code "68") (name "S2_R") (class "Default")
      (node (ref "R34") (pin "2") (pinfunction "2_2") (pintype "passive"))
      (node (ref "S2") (pin "3") (pinfunction "2_3") (pintype "passive"))
    )
    (net (code "69") (name "V3_5") (class "Default")
      (node (ref "R30") (pin "1") (pinfunction "1_1") (pintype "passive"))
      (node (ref "R31") (pin "2") (pinfunction "2_2") (pintype "passive"))
      (node (ref "SJ1") (pin "2") (pinfunction "2_2") (pintype "passive"))
    )
    (net (code "70") (name "VADJ") (class "Default")
      (node (ref "R29") (pin "1") (pinfunction "1_1") (pintype "passive"))
      (node (ref "R30") (pin "2") (pinfunction "2_2") (pintype "passive"))
      (node (ref "U3") (pin "1") (pinfunction "ADJ_1") (pintype "input"))
    )
    (net (code "71") (name "VBIAS") (class "Default")
      (node (ref "R1") (pin "2") (pinfunction "2_2") (pintype "passive"))
      (node (ref "R2") (pin "1") (pinfunction "1_1") (pintype "passive"))
      (node (ref "U$1") (pin "3") (pinfunction "VBIAS_3") (pintype "bidirectional"))
    )
    (net (code "72") (name "VCCD") (class "Default")
      (node (ref "C6") (pin "1") (pinfunction "1_1") (pintype "passive"))
      (node (ref "C7") (pin "1") (pinfunction "1_1") (pintype "passive"))
      (node (ref "U1") (pin "33") (pinfunction "VCCD_33") (pintype "bidirectional"))
    )
    (net (code "73") (name "VDD") (class "Default")
      (node (ref "C1") (pin "1") (pinfunction "1_1") (pintype "passive"))
      (node (ref "C10") (pin "1") (pinfunction "1_1") (pintype "passive"))
      (node (ref "C11") (pin "1") (pinfunction "1_1") (pintype "passive"))
      (node (ref "C2") (pin "1") (pinfunction "1_1") (pintype "passive"))
      (node (ref "C3") (pin "1") (pinfunction "1_1") (pintype "passive"))
      (node (ref "C4") (pin "1") (pinfunction "1_1") (pintype "passive"))
      (node (ref "C5") (pin "1") (pinfunction "1_1") (pintype "passive"))
      (node (ref "C8") (pin "1") (pinfunction "1_1") (pintype "passive"))
      (node (ref "JTAG1") (pin "1") (pinfunction "1_1") (pintype "passive"))
      (node (ref "R10") (pin "1") (pinfunction "1_1") (pintype "passive"))
      (node (ref "R12") (pin "1") (pinfunction "1_1") (pintype "passive"))
      (node (ref "R14") (pin "1") (pinfunction "1_1") (pintype "passive"))
      (node (ref "R16") (pin "2") (pinfunction "2_2") (pintype "passive"))
      (node (ref "R17") (pin "2") (pinfunction "2_2") (pintype "passive"))
      (node (ref "R2") (pin "2") (pinfunction "2_2") (pintype "passive"))
      (node (ref "R20") (pin "1") (pinfunction "1_1") (pintype "passive"))
      (node (ref "R21") (pin "2") (pinfunction "2_2") (pintype "passive"))
      (node (ref "R22") (pin "2") (pinfunction "2_2") (pintype "passive"))
      (node (ref "R28") (pin "2") (pinfunction "2_2") (pintype "passive"))
      (node (ref "R29") (pin "2") (pinfunction "2_2") (pintype "passive"))
      (node (ref "R32") (pin "2") (pinfunction "2_2") (pintype "passive"))
      (node (ref "U$1") (pin "2") (pinfunction "VDD_2") (pintype "power_in"))
      (node (ref "U1") (pin "19") (pinfunction "VDDD_19") (pintype "bidirectional"))
      (node (ref "U1") (pin "34") (pinfunction "VDDD_34") (pintype "bidirectional"))
      (node (ref "U1") (pin "35") (pinfunction "VDDA_35") (pintype "bidirectional"))
      (node (ref "U3") (pin "2") (pinfunction "OUT_2") (pintype "output"))
    )
    (net (code "74") (name "VIN") (class "Default")
      (node (ref "R27") (pin "2") (pinfunction "2_2") (pintype "passive"))
      (node (ref "U2") (pin "VIN") (pinfunction "VIN_VIN") (pintype "bidirectional"))
    )
    (net (code "75") (name "unconnected-(JTAG1-Pad6)") (class "Default")
      (node (ref "JTAG1") (pin "6") (pinfunction "6_6") (pintype "passive"))
    )
    (net (code "76") (name "unconnected-(JTAG1-Pad8)") (class "Default")
      (node (ref "JTAG1") (pin "8") (pinfunction "8_8") (pintype "passive"))
    )
    (net (code "77") (name "unconnected-(U$1-DB0-Pad7)") (class "Default")
      (node (ref "U$1") (pin "7") (pinfunction "DB0_7") (pintype "bidirectional"))
    )
    (net (code "78") (name "unconnected-(U$1-DB1-Pad8)") (class "Default")
      (node (ref "U$1") (pin "8") (pinfunction "DB1_8") (pintype "bidirectional"))
    )
    (net (code "79") (name "unconnected-(U$1-DB2-Pad9)") (class "Default")
      (node (ref "U$1") (pin "9") (pinfunction "DB2_9") (pintype "bidirectional"))
    )
    (net (code "80") (name "unconnected-(U$1-DB3-Pad10)") (class "Default")
      (node (ref "U$1") (pin "10") (pinfunction "DB3_10") (pintype "bidirectional"))
    )
    (net (code "81") (name "unconnected-(U2-Pad2)") (class "Default")
      (node (ref "U2") (pin "2") (pinfunction "2_2") (pintype "bidirectional"))
    )
    (net (code "82") (name "unconnected-(U2-Pad3)") (class "Default")
      (node (ref "U2") (pin "3") (pinfunction "3_3") (pintype "bidirectional"))
    )
    (net (code "83") (name "unconnected-(U2-Pad4)") (class "Default")
      (node (ref "U2") (pin "4") (pinfunction "4_4") (pintype "bidirectional"))
    )
    (net (code "84") (name "unconnected-(U2-Pad5)") (class "Default")
      (node (ref "U2") (pin "5") (pinfunction "5_5") (pintype "bidirectional"))
    )
    (net (code "85") (name "unconnected-(U2-Pad6)") (class "Default")
      (node (ref "U2") (pin "6") (pinfunction "6_6") (pintype "bidirectional"))
    )
    (net (code "86") (name "unconnected-(U2-Pad7)") (class "Default")
      (node (ref "U2") (pin "7") (pinfunction "7_7") (pintype "bidirectional"))
    )
    (net (code "87") (name "unconnected-(U2-Pad8)") (class "Default")
      (node (ref "U2") (pin "8") (pinfunction "8_8") (pintype "bidirectional"))
    )
    (net (code "88") (name "unconnected-(U2-Pad9)") (class "Default")
      (node (ref "U2") (pin "9") (pinfunction "9_9") (pintype "bidirectional"))
    )
    (net (code "89") (name "unconnected-(U2-PadA0)") (class "Default")
      (node (ref "U2") (pin "A0") (pinfunction "A0_A0") (pintype "bidirectional"))
    )
    (net (code "90") (name "unconnected-(U2-PadA1)") (class "Default")
      (node (ref "U2") (pin "A1") (pinfunction "A1_A1") (pintype "bidirectional"))
    )
    (net (code "91") (name "unconnected-(U2-PadA2)") (class "Default")
      (node (ref "U2") (pin "A2") (pinfunction "A2_A2") (pintype "bidirectional"))
    )
    (net (code "92") (name "unconnected-(U2-PadA3)") (class "Default")
      (node (ref "U2") (pin "A3") (pinfunction "A3_A3") (pintype "bidirectional"))
    )
    (net (code "93") (name "unconnected-(U2-PadA4)") (class "Default")
      (node (ref "U2") (pin "A4") (pinfunction "A4_A4") (pintype "bidirectional"))
    )
    (net (code "94") (name "unconnected-(U2-PadA5)") (class "Default")
      (node (ref "U2") (pin "A5") (pinfunction "A5_A5") (pintype "bidirectional"))
    )
    (net (code "95") (name "unconnected-(U2-PadA6)") (class "Default")
      (node (ref "U2") (pin "A6") (pinfunction "A6_A6") (pintype "bidirectional"))
    )
    (net (code "96") (name "unconnected-(U2-PadA7)") (class "Default")
      (node (ref "U2") (pin "A7") (pinfunction "A7_A7") (pintype "bidirectional"))
    )
    (net (code "97") (name "~{XRES}") (class "Default")
      (node (ref "JTAG1") (pin "10") (pinfunction "10_10") (pintype "passive"))
      (node (ref "R20") (pin "2") (pinfunction "2_2") (pintype "passive"))
      (node (ref "U1") (pin "32") (pinfunction "~{XRES}_32") (pintype "bidirectional"))
      (node (ref "U2") (pin "RESET") (pinfunction "RESET_RESET") (pintype "bidirectional"))
    )
  )
)
